# schemetric.net
KiCad netlist of a schematic drawn in Altium Designer
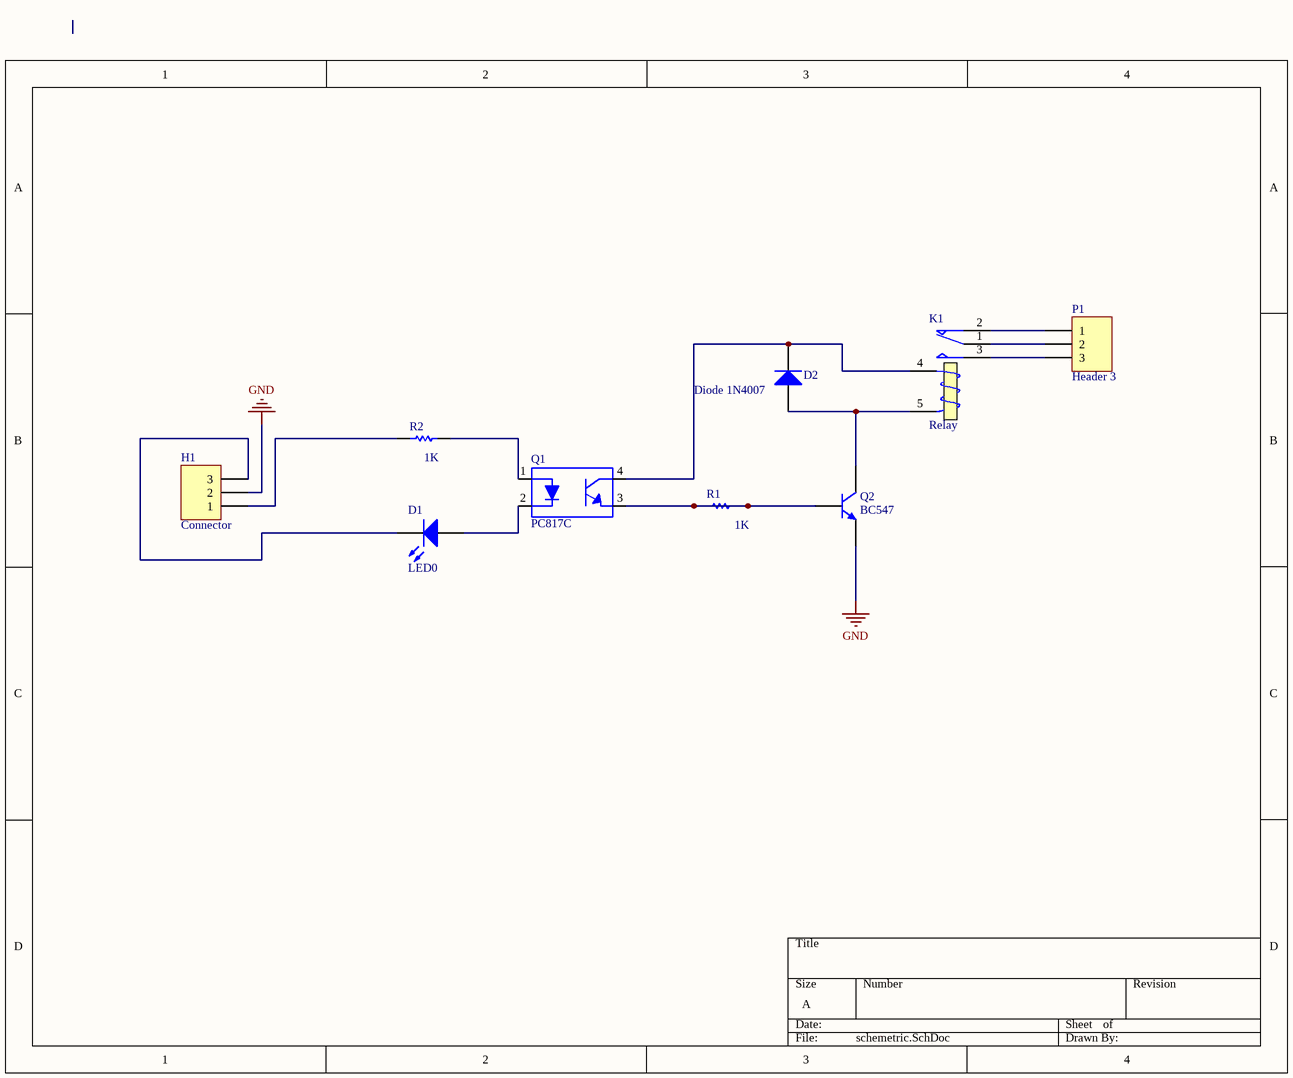
[diagram p0: schemetric.SchDoc]

(export (version "E")
  (design (tool "Eeschema 10.0.6"))
  (components
    (comp (ref "D1")
      (value "LED0")
      (footprint "LED-0")
      (description "Typical INFRARED GaAs LED")
      (fields (field (name "PUBLISHER") "Altium Limited"))
      (libsource (lib "Miscellaneous Devices") (part "LED0"))
    )
    (comp (ref "D2")
      (value "Diode 1N4007")
      (footprint "DO-41")
      (description "1 Amp General Purpose Rectifier")
      (fields (field (name "PUBLISHER") "Altium Limited"))
      (libsource (lib "Miscellaneous Devices") (part "Diode 1N4007"))
    )
    (comp (ref "H1")
      (value "Connector")
      (footprint "HDR1X3")
      (description "Header, 3-Pin")
      (fields (field (name "PUBLISHER") "Altium Limited"))
      (libsource (lib "Miscellaneous Connectors") (part "Header 3"))
    )
    (comp (ref "K1")
      (value "Relay")
      (footprint "MODULE5B")
      (description "SPDT Relay")
      (fields (field (name "PUBLISHER") "Altium Limited"))
      (libsource (lib "Miscellaneous Devices") (part "Relay"))
    )
    (comp (ref "P1")
      (value "Header 3")
      (footprint "HDR1X3")
      (description "Header, 3-Pin")
      (fields (field (name "PUBLISHER") "Altium Limited"))
      (libsource (lib "") (part "Header 3_1"))
    )
    (comp (ref "Q1")
      (value "PC817C")
      (footprint "PC817-DIP")
      (description "Optoisolator Transistor Output 5000Vrms 1 Channel 4-DIP\r\n¦ Designed By @Alixahedi ¦")
      (fields (field (name "MF") "Taiwan Semiconductor"))
      (libsource (lib "PC817C") (part "PC817C"))
    )
    (comp (ref "Q2")
      (value "BC547")
      (footprint "TO-226-AA")
      (description "NPN Bipolar Transistor")
      (fields (field (name "PUBLISHER") "Altium Limited"))
      (libsource (lib "Miscellaneous Devices") (part "NPN"))
    )
    (comp (ref "R1")
      (value "1K")
      (footprint "AXIAL-0.3")
      (description "Resistor")
      (fields (field (name "PUBLISHER") "Altium Limited"))
      (libsource (lib "Miscellaneous Devices") (part "Res1"))
    )
    (comp (ref "R2")
      (value "1K")
      (footprint "AXIAL-0.3")
      (description "Resistor")
      (fields (field (name "PUBLISHER") "Altium Limited"))
      (libsource (lib "Miscellaneous Devices") (part "Res1"))
    )
  )
  (nets
    (net (code "1") (name "GND") (class "Default")
      (node (ref "H1") (pin "2") (pinfunction "2_2") (pintype "passive"))
      (node (ref "Q2") (pin "3") (pinfunction "E_3") (pintype "passive"))
    )
    (net (code "2") (name "Net-(D1-A)") (class "Default")
      (node (ref "D1") (pin "1") (pinfunction "A_1") (pintype "passive"))
      (node (ref "Q1") (pin "2") (pinfunction "2_2") (pintype "passive"))
    )
    (net (code "3") (name "Net-(D1-K)") (class "Default")
      (node (ref "D1") (pin "2") (pinfunction "K_2") (pintype "passive"))
      (node (ref "H1") (pin "3") (pinfunction "3_3") (pintype "passive"))
    )
    (net (code "4") (name "Net-(D2-A)") (class "Default")
      (node (ref "D2") (pin "1") (pinfunction "A_1") (pintype "passive"))
      (node (ref "K1") (pin "5") (pinfunction "T2_5") (pintype "passive"))
      (node (ref "Q2") (pin "1") (pinfunction "C_1") (pintype "passive"))
    )
    (net (code "5") (name "Net-(D2-K)") (class "Default")
      (node (ref "D2") (pin "2") (pinfunction "K_2") (pintype "passive"))
      (node (ref "K1") (pin "4") (pinfunction "T1_4") (pintype "passive"))
      (node (ref "Q1") (pin "4") (pinfunction "4_4") (pintype "passive"))
    )
    (net (code "6") (name "Net-(H1-Pad1)") (class "Default")
      (node (ref "H1") (pin "1") (pinfunction "1_1") (pintype "passive"))
      (node (ref "R2") (pin "1") (pinfunction "1_1") (pintype "passive"))
    )
    (net (code "7") (name "Net-(K1-COM)") (class "Default")
      (node (ref "K1") (pin "1") (pinfunction "COM_1") (pintype "passive"))
      (node (ref "P1") (pin "2") (pinfunction "2_2") (pintype "passive"))
    )
    (net (code "8") (name "Net-(K1-NC)") (class "Default")
      (node (ref "K1") (pin "2") (pinfunction "NC_2") (pintype "passive"))
      (node (ref "P1") (pin "1") (pinfunction "1_1") (pintype "passive"))
    )
    (net (code "9") (name "Net-(K1-NO)") (class "Default")
      (node (ref "K1") (pin "3") (pinfunction "NO_3") (pintype "passive"))
      (node (ref "P1") (pin "3") (pinfunction "3_3") (pintype "passive"))
    )
    (net (code "10") (name "Net-(Q1-Pad1)") (class "Default")
      (node (ref "Q1") (pin "1") (pinfunction "1_1") (pintype "passive"))
      (node (ref "R2") (pin "2") (pinfunction "2_2") (pintype "passive"))
    )
    (net (code "11") (name "Net-(Q2-B)") (class "Default")
      (node (ref "Q1") (pin "3") (pinfunction "3_3") (pintype "passive"))
      (node (ref "Q2") (pin "2") (pinfunction "B_2") (pintype "passive"))
      (node (ref "R1") (pin "1") (pinfunction "1_1") (pintype "passive"))
      (node (ref "R1") (pin "2") (pinfunction "2_2") (pintype "passive"))
    )
  )
)
